# analog.net
KiCad netlist of a schematic drawn in Altium Designer
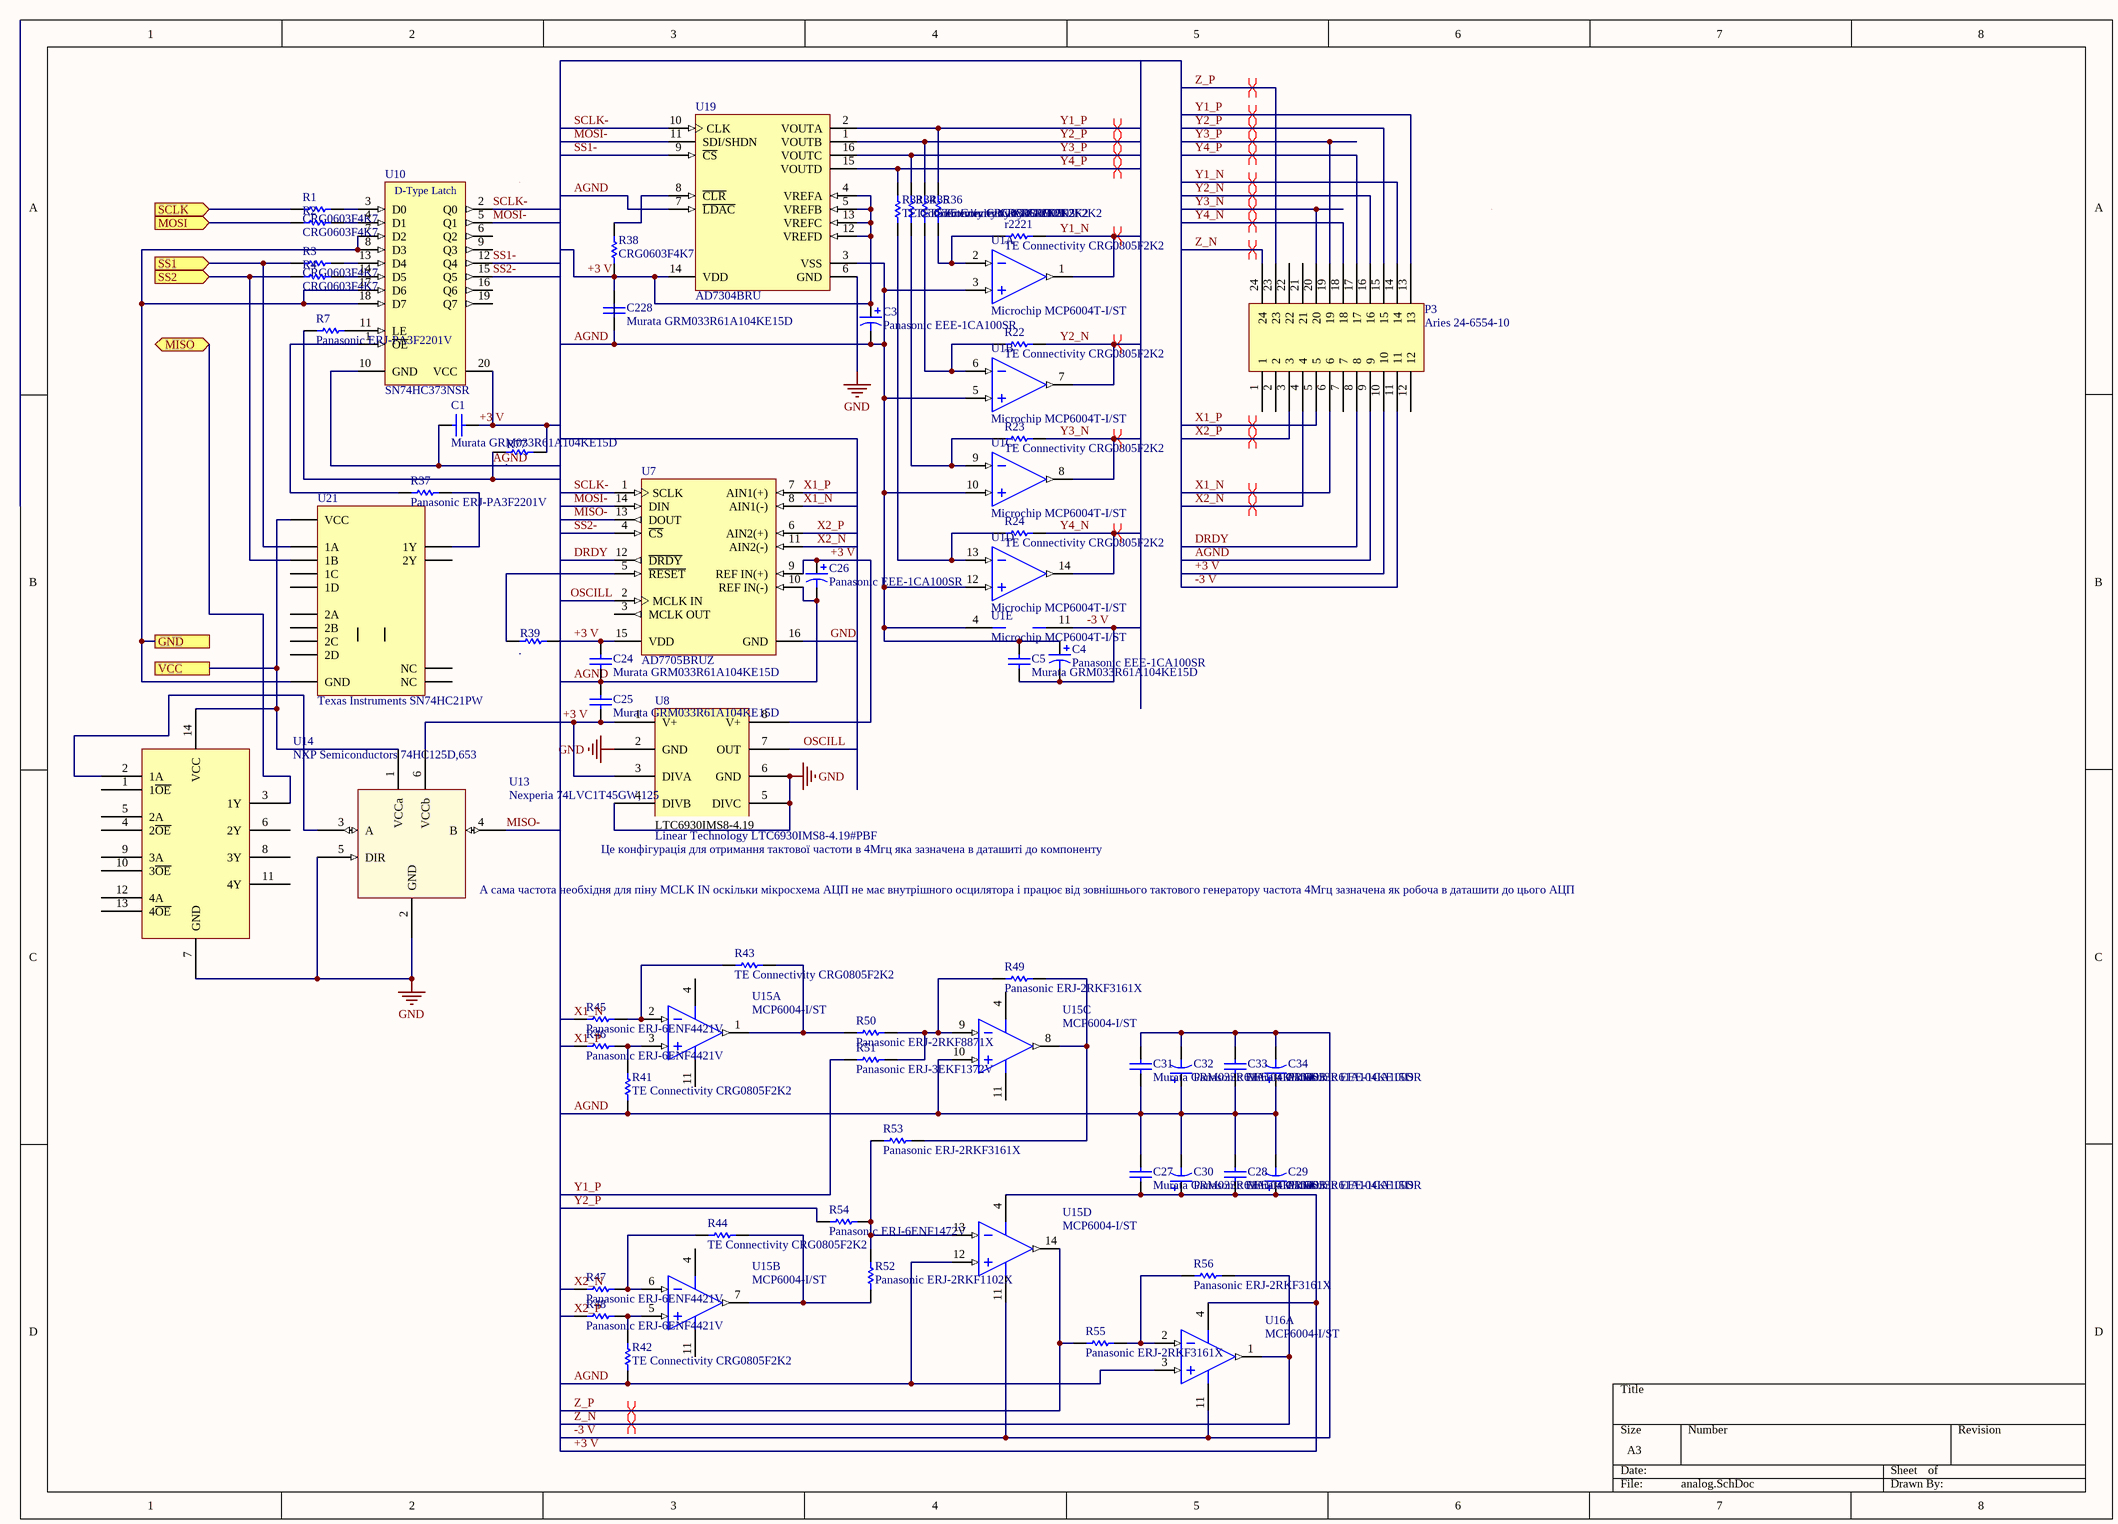
[diagram p0: analog.SchDoc]

(export (version "E")
  (design (tool "Eeschema 10.0.6"))
  (components
    (comp (ref "C1")
      (value "Murata GRM033R61A104KE15D")
      (footprint "201-cap")
      (description "Cap Ceramic 0.1uF 10V X5R 10% SMD 0201 85C Paper T/R")
      (fields (field (name "MANUFACTURER PART NUMBER") "GRM033R61A104KE15D"))
      (libsource (lib "My Personal Space") (part "GRM033R61A104KE15D"))
    )
    (comp (ref "C3")
      (value "Panasonic EEE-1CA100SR")
      (footprint "PCB-5c7lwdch6d5n3jfyiyq6-1")
      (description "Capacitor Alum Elec, 10uf, 16v, 20%, Scapacitor Alum Elec, 10uf, 16v, 20%, Smd, Full Reel")
      (libsource (lib "My Personal Space") (part "SYM-1d6cd72bfd77c2ab-3"))
    )
    (comp (ref "C4")
      (value "Panasonic EEE-1CA100SR")
      (footprint "PCB-5c7lwdch6d5n3jfyiyq6-1")
      (description "Capacitor Alum Elec, 10uf, 16v, 20%, Scapacitor Alum Elec, 10uf, 16v, 20%, Smd, Full Reel")
      (libsource (lib "My Personal Space") (part "SYM-1d6cd72bfd77c2ab-3"))
    )
    (comp (ref "C5")
      (value "Murata GRM033R61A104KE15D")
      (footprint "201-cap")
      (description "Cap Ceramic 0.1uF 10V X5R 10% SMD 0201 85C Paper T/R")
      (fields (field (name "MANUFACTURER PART NUMBER") "GRM033R61A104KE15D"))
      (libsource (lib "My Personal Space") (part "GRM033R61A104KE15D"))
    )
    (comp (ref "C24")
      (value "Murata GRM033R61A104KE15D")
      (footprint "201-cap")
      (description "Cap Ceramic 0.1uF 10V X5R 10% SMD 0201 85C Paper T/R")
      (fields (field (name "MANUFACTURER PART NUMBER") "GRM033R61A104KE15D"))
      (libsource (lib "My Personal Space") (part "GRM033R61A104KE15D"))
    )
    (comp (ref "C25")
      (value "Murata GRM033R61A104KE15D")
      (footprint "201-cap")
      (description "Cap Ceramic 0.1uF 10V X5R 10% SMD 0201 85C Paper T/R")
      (fields (field (name "MANUFACTURER PART NUMBER") "GRM033R61A104KE15D"))
      (libsource (lib "My Personal Space") (part "GRM033R61A104KE15D"))
    )
    (comp (ref "C26")
      (value "Panasonic EEE-1CA100SR")
      (footprint "PCB-5c7lwdch6d5n3jfyiyq6-1")
      (description "Capacitor Alum Elec, 10uf, 16v, 20%, Scapacitor Alum Elec, 10uf, 16v, 20%, Smd, Full Reel")
      (libsource (lib "My Personal Space") (part "SYM-1d6cd72bfd77c2ab-3"))
    )
    (comp (ref "C27")
      (value "Murata GRM033R61A104KE15D")
      (footprint "201-cap")
      (description "Cap Ceramic 0.1uF 10V X5R 10% SMD 0201 85C Paper T/R")
      (fields (field (name "MANUFACTURER PART NUMBER") "GRM033R61A104KE15D"))
      (libsource (lib "My Personal Space") (part "GRM033R61A104KE15D"))
    )
    (comp (ref "C28")
      (value "Murata GRM033R61A104KE15D")
      (footprint "201-cap")
      (description "Cap Ceramic 0.1uF 10V X5R 10% SMD 0201 85C Paper T/R")
      (fields (field (name "MANUFACTURER PART NUMBER") "GRM033R61A104KE15D"))
      (libsource (lib "My Personal Space") (part "GRM033R61A104KE15D"))
    )
    (comp (ref "C29")
      (value "Panasonic EEE-1CA100SR")
      (footprint "PCB-5c7lwdch6d5n3jfyiyq6-1")
      (description "Capacitor Alum Elec, 10uf, 16v, 20%, Scapacitor Alum Elec, 10uf, 16v, 20%, Smd, Full Reel")
      (libsource (lib "My Personal Space") (part "SYM-1d6cd72bfd77c2ab-3"))
    )
    (comp (ref "C30")
      (value "Panasonic EEE-1CA100SR")
      (footprint "PCB-5c7lwdch6d5n3jfyiyq6-1")
      (description "Capacitor Alum Elec, 10uf, 16v, 20%, Scapacitor Alum Elec, 10uf, 16v, 20%, Smd, Full Reel")
      (libsource (lib "My Personal Space") (part "SYM-1d6cd72bfd77c2ab-3"))
    )
    (comp (ref "C31")
      (value "Murata GRM033R61A104KE15D")
      (footprint "201-cap")
      (description "Cap Ceramic 0.1uF 10V X5R 10% SMD 0201 85C Paper T/R")
      (fields (field (name "MANUFACTURER PART NUMBER") "GRM033R61A104KE15D"))
      (libsource (lib "My Personal Space") (part "GRM033R61A104KE15D"))
    )
    (comp (ref "C32")
      (value "Panasonic EEE-1CA100SR")
      (footprint "PCB-5c7lwdch6d5n3jfyiyq6-1")
      (description "Capacitor Alum Elec, 10uf, 16v, 20%, Scapacitor Alum Elec, 10uf, 16v, 20%, Smd, Full Reel")
      (libsource (lib "My Personal Space") (part "SYM-1d6cd72bfd77c2ab-3"))
    )
    (comp (ref "C33")
      (value "Murata GRM033R61A104KE15D")
      (footprint "201-cap")
      (description "Cap Ceramic 0.1uF 10V X5R 10% SMD 0201 85C Paper T/R")
      (fields (field (name "MANUFACTURER PART NUMBER") "GRM033R61A104KE15D"))
      (libsource (lib "My Personal Space") (part "GRM033R61A104KE15D"))
    )
    (comp (ref "C34")
      (value "Panasonic EEE-1CA100SR")
      (footprint "PCB-5c7lwdch6d5n3jfyiyq6-1")
      (description "Capacitor Alum Elec, 10uf, 16v, 20%, Scapacitor Alum Elec, 10uf, 16v, 20%, Smd, Full Reel")
      (libsource (lib "My Personal Space") (part "SYM-1d6cd72bfd77c2ab-3"))
    )
    (comp (ref "C228")
      (value "Murata GRM033R61A104KE15D")
      (footprint "201-cap")
      (description "Cap Ceramic 0.1uF 10V X5R 10% SMD 0201 85C Paper T/R")
      (fields (field (name "MANUFACTURER PART NUMBER") "GRM033R61A104KE15D"))
      (libsource (lib "My Personal Space") (part "GRM033R61A104KE15D"))
    )
    (comp (ref "P3")
      (value "Aries 24-6554-10")
      (footprint "PCB-ekyruasckp3dwikngkzw-1")
      (description "Connector Test Socket Receptacle 24 Position 2.54mm Solder Straight Thru-Hole")
      (fields (field (name "MANUFACTURER PART NUMBER") "24-6554-10"))
      (libsource (lib "My Personal Space") (part "SYM-1a82d3838c70c545-1"))
    )
    (comp (ref "R1")
      (value "CRG0603F4K7")
      (footprint "RESC1609X50X30ML10T20")
      (description "Res Thick Film 0603 4.7K Ohm 1% 0.1W(1/10W) ±100ppm/C Pad SMD T/R")
      (libsource (lib "") (part "RES-2_1"))
    )
    (comp (ref "R2")
      (value "CRG0603F4K7")
      (footprint "RESC1609X50X30ML10T20")
      (description "Res Thick Film 0603 4.7K Ohm 1% 0.1W(1/10W) ±100ppm/C Pad SMD T/R")
      (libsource (lib "") (part "RES-2_1"))
    )
    (comp (ref "R3")
      (value "CRG0603F4K7")
      (footprint "RESC1609X50X30ML10T20")
      (description "Res Thick Film 0603 4.7K Ohm 1% 0.1W(1/10W) ±100ppm/C Pad SMD T/R")
      (libsource (lib "") (part "RES-2_1"))
    )
    (comp (ref "R4")
      (value "CRG0603F4K7")
      (footprint "RESC1609X50X30ML10T20")
      (description "Res Thick Film 0603 4.7K Ohm 1% 0.1W(1/10W) ±100ppm/C Pad SMD T/R")
      (libsource (lib "") (part "RES-2_1"))
    )
    (comp (ref "R7")
      (value "Panasonic ERJ-PA3F2201V")
      (footprint "RESC1608X55X30LL15T15")
      (description "Res Thick Film 0603 2.2K Ohm 1% 0.25W(1/4W) ±100ppm/C Pad SMD Automotive T/R")
      (fields (field (name "MANUFACTURER PART NUMBER") "ERJ-PA3F2201V"))
      (libsource (lib "My Personal Space") (part "RES-2"))
    )
    (comp (ref "R22")
      (value "TE Connectivity CRG0805F2K2")
      (footprint "RESC3216X70X50LL05T20")
      (description "Res Thick Film 0805 2.2K Ohm 1% 0.125W(1/8W) ±100ppm/C Pad SMD T/R")
      (fields (field (name "MANUFACTURER PART NUMBER") "CRG0805F2K2"))
      (libsource (lib "My Personal Space") (part "RES-2"))
    )
    (comp (ref "R23")
      (value "TE Connectivity CRG0805F2K2")
      (footprint "RESC3216X70X50LL05T20")
      (description "Res Thick Film 0805 2.2K Ohm 1% 0.125W(1/8W) ±100ppm/C Pad SMD T/R")
      (fields (field (name "MANUFACTURER PART NUMBER") "CRG0805F2K2"))
      (libsource (lib "My Personal Space") (part "RES-2"))
    )
    (comp (ref "R24")
      (value "TE Connectivity CRG0805F2K2")
      (footprint "RESC3216X70X50LL05T20")
      (description "Res Thick Film 0805 2.2K Ohm 1% 0.125W(1/8W) ±100ppm/C Pad SMD T/R")
      (fields (field (name "MANUFACTURER PART NUMBER") "CRG0805F2K2"))
      (libsource (lib "My Personal Space") (part "RES-2"))
    )
    (comp (ref "R33")
      (value "TE Connectivity CRG0805F2K2")
      (footprint "RESC3216X70X50LL05T20")
      (description "Res Thick Film 0805 2.2K Ohm 1% 0.125W(1/8W) ±100ppm/C Pad SMD T/R")
      (fields (field (name "MANUFACTURER PART NUMBER") "CRG0805F2K2"))
      (libsource (lib "My Personal Space") (part "RES-2"))
    )
    (comp (ref "R34")
      (value "TE Connectivity CRG0805F2K2")
      (footprint "RESC3216X70X50LL05T20")
      (description "Res Thick Film 0805 2.2K Ohm 1% 0.125W(1/8W) ±100ppm/C Pad SMD T/R")
      (fields (field (name "MANUFACTURER PART NUMBER") "CRG0805F2K2"))
      (libsource (lib "My Personal Space") (part "RES-2"))
    )
    (comp (ref "R35")
      (value "TE Connectivity CRG0805F2K2")
      (footprint "RESC3216X70X50LL05T20")
      (description "Res Thick Film 0805 2.2K Ohm 1% 0.125W(1/8W) ±100ppm/C Pad SMD T/R")
      (fields (field (name "MANUFACTURER PART NUMBER") "CRG0805F2K2"))
      (libsource (lib "My Personal Space") (part "RES-2"))
    )
    (comp (ref "R36")
      (value "TE Connectivity CRG0805F2K2")
      (footprint "RESC3216X70X50LL05T20")
      (description "Res Thick Film 0805 2.2K Ohm 1% 0.125W(1/8W) ±100ppm/C Pad SMD T/R")
      (fields (field (name "MANUFACTURER PART NUMBER") "CRG0805F2K2"))
      (libsource (lib "My Personal Space") (part "RES-2"))
    )
    (comp (ref "R37")
      (value "Panasonic ERJ-PA3F2201V")
      (footprint "RESC1608X55X30LL15T15")
      (description "Res Thick Film 0603 2.2K Ohm 1% 0.25W(1/4W) ±100ppm/C Pad SMD Automotive T/R")
      (fields (field (name "MANUFACTURER PART NUMBER") "ERJ-PA3F2201V"))
      (libsource (lib "My Personal Space") (part "RES-2"))
    )
    (comp (ref "R38")
      (value "CRG0603F4K7")
      (footprint "RESC1609X50X30ML10T20")
      (description "Res Thick Film 0603 4.7K Ohm 1% 0.1W(1/10W) ±100ppm/C Pad SMD T/R")
      (libsource (lib "") (part "RES-2_1"))
    )
    (comp (ref "R39")
      (value ".")
      (footprint "RESC1608X55X30LL15T15")
      (description "Res Thick Film 0603 2.2K Ohm 1% 0.25W(1/4W) ±100ppm/C Pad SMD Automotive T/R")
      (fields (field (name "MANUFACTURER PART NUMBER") "ERJ-PA3F2201V"))
      (libsource (lib "My Personal Space") (part "RES-2"))
    )
    (comp (ref "R41")
      (value "TE Connectivity CRG0805F2K2")
      (footprint "RESC3216X70X50LL05T20")
      (description "Res Thick Film 0805 2.2K Ohm 1% 0.125W(1/8W) ±100ppm/C Pad SMD T/R")
      (fields (field (name "MANUFACTURER PART NUMBER") "CRG0805F2K2"))
      (libsource (lib "My Personal Space") (part "RES-2"))
    )
    (comp (ref "R42")
      (value "TE Connectivity CRG0805F2K2")
      (footprint "RESC3216X70X50LL05T20")
      (description "Res Thick Film 0805 2.2K Ohm 1% 0.125W(1/8W) ±100ppm/C Pad SMD T/R")
      (fields (field (name "MANUFACTURER PART NUMBER") "CRG0805F2K2"))
      (libsource (lib "My Personal Space") (part "RES-2"))
    )
    (comp (ref "R43")
      (value "TE Connectivity CRG0805F2K2")
      (footprint "RESC3216X70X50LL05T20")
      (description "Res Thick Film 0805 2.2K Ohm 1% 0.125W(1/8W) ±100ppm/C Pad SMD T/R")
      (fields (field (name "MANUFACTURER PART NUMBER") "CRG0805F2K2"))
      (libsource (lib "My Personal Space") (part "RES-2"))
    )
    (comp (ref "R44")
      (value "TE Connectivity CRG0805F2K2")
      (footprint "RESC3216X70X50LL05T20")
      (description "Res Thick Film 0805 2.2K Ohm 1% 0.125W(1/8W) ±100ppm/C Pad SMD T/R")
      (fields (field (name "MANUFACTURER PART NUMBER") "CRG0805F2K2"))
      (libsource (lib "My Personal Space") (part "RES-2"))
    )
    (comp (ref "R45")
      (value "Panasonic ERJ-6ENF4421V")
      (footprint "RESC2013X70X40ML20T20")
      (description "RESISTOR, THICK FILM, 4.42KOHM, 125mW, ± 1%")
      (fields (field (name "MANUFACTURER PART NUMBER") "ERJ-6ENF4421V"))
      (libsource (lib "My Personal Space") (part "RES-2"))
    )
    (comp (ref "R46")
      (value "Panasonic ERJ-6ENF4421V")
      (footprint "RESC2013X70X40ML20T20")
      (description "RESISTOR, THICK FILM, 4.42KOHM, 125mW, ± 1%")
      (fields (field (name "MANUFACTURER PART NUMBER") "ERJ-6ENF4421V"))
      (libsource (lib "My Personal Space") (part "RES-2"))
    )
    (comp (ref "R47")
      (value "Panasonic ERJ-6ENF4421V")
      (footprint "RESC2013X70X40ML20T20")
      (description "RESISTOR, THICK FILM, 4.42KOHM, 125mW, ± 1%")
      (fields (field (name "MANUFACTURER PART NUMBER") "ERJ-6ENF4421V"))
      (libsource (lib "My Personal Space") (part "RES-2"))
    )
    (comp (ref "R48")
      (value "Panasonic ERJ-6ENF4421V")
      (footprint "RESC2013X70X40ML20T20")
      (description "RESISTOR, THICK FILM, 4.42KOHM, 125mW, ± 1%")
      (fields (field (name "MANUFACTURER PART NUMBER") "ERJ-6ENF4421V"))
      (libsource (lib "My Personal Space") (part "RES-2"))
    )
    (comp (ref "R49")
      (value "Panasonic ERJ-2RKF3161X")
      (footprint "RESC1005X40X25ML05T05")
      (description "Thick Film Resistors - SMD 0402 3.16Kohms 1% Tol")
      (fields (field (name "MANUFACTURER PART NUMBER") "ERJ-2RKF3161X"))
      (libsource (lib "My Personal Space") (part "RES-2"))
    )
    (comp (ref "R50")
      (value "Panasonic ERJ-2RKF8871X")
      (footprint "RESC1005X40X25ML05T05")
      (description "Thick Film Resistors - SMD 0402 8.87Kohms 1% Tol")
      (fields (field (name "MANUFACTURER PART NUMBER") "ERJ-2RKF8871X"))
      (libsource (lib "My Personal Space") (part "RES-2"))
    )
    (comp (ref "R51")
      (value "Panasonic ERJ-3EKF1372V")
      (footprint "RESC1608X55X30LL15T15")
      (description "Thick Film Resistors - SMD 0603 13.7Kohms 1% Tol")
      (fields (field (name "MANUFACTURER PART NUMBER") "ERJ-3EKF1372V"))
      (libsource (lib "My Personal Space") (part "RES-2"))
    )
    (comp (ref "R52")
      (value "Panasonic ERJ-2RKF1102X")
      (footprint "RESC1005X40X25ML05T05")
      (description "Res Thick Film 0402 11K Ohm 1% 1/10W ±100ppm/C Molded SMD Punched Carrier T/R")
      (fields (field (name "MANUFACTURER PART NUMBER") "ERJ-2RKF1102X"))
      (libsource (lib "My Personal Space") (part "RES-2"))
    )
    (comp (ref "R53")
      (value "Panasonic ERJ-2RKF3161X")
      (footprint "RESC1005X40X25ML05T05")
      (description "Thick Film Resistors - SMD 0402 3.16Kohms 1% Tol")
      (fields (field (name "MANUFACTURER PART NUMBER") "ERJ-2RKF3161X"))
      (libsource (lib "My Personal Space") (part "RES-2"))
    )
    (comp (ref "R54")
      (value "Panasonic ERJ-6ENF1472V")
      (footprint "RESC2013X70X40LL20T20")
      (description "Thick Film Resistors - SMD 0805 14.7Kohms 1% Tol")
      (fields (field (name "MANUFACTURER PART NUMBER") "ERJ-6ENF1472V"))
      (libsource (lib "My Personal Space") (part "RES-2"))
    )
    (comp (ref "R55")
      (value "Panasonic ERJ-2RKF3161X")
      (footprint "RESC1005X40X25ML05T05")
      (description "Thick Film Resistors - SMD 0402 3.16Kohms 1% Tol")
      (fields (field (name "MANUFACTURER PART NUMBER") "ERJ-2RKF3161X"))
      (libsource (lib "My Personal Space") (part "RES-2"))
    )
    (comp (ref "R56")
      (value "Panasonic ERJ-2RKF3161X")
      (footprint "RESC1005X40X25ML05T05")
      (description "Thick Film Resistors - SMD 0402 3.16Kohms 1% Tol")
      (fields (field (name "MANUFACTURER PART NUMBER") "ERJ-2RKF3161X"))
      (libsource (lib "My Personal Space") (part "RES-2"))
    )
    (comp (ref "R77")
      (value ".")
      (footprint "RESC1608X55X30LL15T15")
      (description "Res Thick Film 0603 2.2K Ohm 1% 0.25W(1/4W) ±100ppm/C Pad SMD Automotive T/R")
      (fields (field (name "MANUFACTURER PART NUMBER") "ERJ-PA3F2201V"))
      (libsource (lib "My Personal Space") (part "RES-2"))
    )
    (comp (ref "r2221")
      (value "TE Connectivity CRG0805F2K2")
      (footprint "RESC3216X70X50LL05T20")
      (description "Res Thick Film 0805 2.2K Ohm 1% 0.125W(1/8W) ±100ppm/C Pad SMD T/R")
      (fields (field (name "MANUFACTURER PART NUMBER") "CRG0805F2K2"))
      (libsource (lib "My Personal Space") (part "RES-2"))
    )
    (comp (ref "U1")
      (value "Microchip MCP6004T-I/ST")
      (footprint "PCB-qd5l9gv8ivpyuc7qt6ns-1")
      (description "MCP6004 Series 6 V 1 MHz SMT Low-Power Operational Amplifier - TSSOP-14")
      (libsource (lib "My Personal Space") (part "SYM-2145e8496108fe82-3"))
    )
    (comp (ref "U7")
      (value "AD7705BRUZ")
      (footprint "RU-16_N")
      (libsource (lib "My Personal Space") (part "ADI-AD7705-RU-16"))
    )
    (comp (ref "U8")
      (value "Linear Technology LTC6930IMS8-4.19#PBF")
      (footprint "PCB-f6jmd1xdx0tvjqeq7wyy-1")
      (fields (field (name "MANUFACTURER PART NUMBER") "LTC6930IMS8-5.00#PBF"))
      (libsource (lib "My Personal Space") (part "SYM-b5277c902da26ae0-1"))
    )
    (comp (ref "U10")
      (value "SN74HC373NSR")
      (footprint "PCB-mrivl7f71t22rnyfb9oh-1")
      (description "Octal Transparent D-Type Latches With 3-State Outputs 20-SO -40 to 85")
      (libsource (lib "My Personal Space") (part "SYM-209beb569da8ff5c-1"))
    )
    (comp (ref "U13")
      (value "Nexperia 74LVC1T45GW,125")
      (footprint "PCB-2kx227qvn7pif93bx96a-1")
      (description "74LVC1T45; 74LVCH1T45 - Dual supply translating transceiver; 3-state")
      (fields (field (name "MANUFACTURER PART NUMBER") "74LVC1T45GW,125"))
      (libsource (lib "My Personal Space") (part "SYM-9dea5051caa8422d-1"))
    )
    (comp (ref "U14")
      (value "NXP Semiconductors 74HC125D,653")
      (footprint "SO14")
      (description "74HC Series 6 V Surface Mount 3-State Quad Buffer/Line Driver - SOIC-14")
      (fields (field (name "MANUFACTURER PART NUMBER") "74HC125D,653"))
      (libsource (lib "My Personal Space") (part "SYM-e63b2fae16a839fc-1"))
    )
    (comp (ref "U15")
      (value "MCP6004-I/ST")
      (footprint "TSSOP-ST14_L")
      (description "1 MHz, Low-Power Operational Amplifier, 14-Pin TSSOP, Industrial Temperature")
      (libsource (lib "My Personal Space") (part "AMP-OPA-MCP6004-IL14"))
    )
    (comp (ref "U16")
      (value "MCP6004-I/ST")
      (footprint "TSSOP-ST14_L")
      (description "1 MHz, Low-Power Operational Amplifier, 14-Pin TSSOP, Industrial Temperature")
      (libsource (lib "My Personal Space") (part "AMP-OPA-MCP6004-IL14"))
    )
    (comp (ref "U19")
      (value "AD7304BRU")
      (footprint "RU-16_M")
      (libsource (lib "My Personal Space") (part "ADI-AD7304-RU-16"))
    )
    (comp (ref "U21")
      (value "Texas Instruments SN74HC21PW")
      (footprint "PCB-zlibg0os7u66y1b7c6dv-1")
      (description "AND Gate 2-Element 4-IN CMOS 14-Pin TSSOP Tube")
      (fields (field (name "MANUFACTURER PART NUMBER") "SN74HC21PW"))
      (libsource (lib "My Personal Space") (part "SYM-6615af12324ab9d2-2"))
    )
  )
  (nets
    (net (code "1") (name "/+3 V") (class "Default")
      (node (ref "C1") (pin "2") (pinfunction "2_2") (pintype "passive"))
      (node (ref "C228") (pin "1") (pinfunction "1_1") (pintype "passive"))
      (node (ref "C24") (pin "1") (pinfunction "1_1") (pintype "passive"))
      (node (ref "C25") (pin "2") (pinfunction "2_2") (pintype "passive"))
      (node (ref "C26") (pin "1") (pinfunction "1_1") (pintype "passive"))
      (node (ref "C27") (pin "2") (pinfunction "2_2") (pintype "passive"))
      (node (ref "C28") (pin "2") (pinfunction "2_2") (pintype "passive"))
      (node (ref "C29") (pin "1") (pinfunction "1_1") (pintype "passive"))
      (node (ref "C3") (pin "1") (pinfunction "1_1") (pintype "passive"))
      (node (ref "C30") (pin "1") (pinfunction "1_1") (pintype "passive"))
      (node (ref "P3") (pin "10") (pinfunction "10_10") (pintype "passive"))
      (node (ref "R38") (pin "1") (pinfunction "1_1") (pintype "passive"))
      (node (ref "R39") (pin "2") (pinfunction "2_2") (pintype "passive"))
      (node (ref "R77") (pin "2") (pinfunction "2_2") (pintype "passive"))
      (node (ref "U10") (pin "20") (pinfunction "VCC_20") (pintype "power_in"))
      (node (ref "U13") (pin "6") (pinfunction "VCCb_6") (pintype "power_in"))
      (node (ref "U15") (pin "4") (pinfunction "VDD_4") (pintype "power_in"))
      (node (ref "U16") (pin "4") (pinfunction "VDD_4") (pintype "power_in"))
      (node (ref "U19") (pin "12") (pinfunction "VREFD_12") (pintype "input"))
      (node (ref "U19") (pin "13") (pinfunction "VREFC_13") (pintype "input"))
      (node (ref "U19") (pin "14") (pinfunction "VDD_14") (pintype "power_in"))
      (node (ref "U19") (pin "4") (pinfunction "VREFA_4") (pintype "input"))
      (node (ref "U19") (pin "5") (pinfunction "VREFB_5") (pintype "input"))
      (node (ref "U7") (pin "15") (pinfunction "VDD_15") (pintype "power_in"))
      (node (ref "U7") (pin "9") (pinfunction "REF_IN(+)_9") (pintype "input"))
      (node (ref "U8") (pin "1") (pinfunction "V+_1") (pintype "passive"))
      (node (ref "U8") (pin "3") (pinfunction "DIVA_3") (pintype "passive"))
      (node (ref "U8") (pin "8") (pinfunction "V+_8") (pintype "passive"))
    )
    (net (code "2") (name "/-3 V") (class "Default")
      (node (ref "C31") (pin "1") (pinfunction "1_1") (pintype "passive"))
      (node (ref "C32") (pin "2") (pinfunction "2_2") (pintype "passive"))
      (node (ref "C33") (pin "1") (pinfunction "1_1") (pintype "passive"))
      (node (ref "C34") (pin "2") (pinfunction "2_2") (pintype "passive"))
      (node (ref "C4") (pin "2") (pinfunction "2_2") (pintype "passive"))
      (node (ref "C5") (pin "2") (pinfunction "2_2") (pintype "passive"))
      (node (ref "P3") (pin "11") (pinfunction "11_11") (pintype "passive"))
      (node (ref "U1") (pin "11") (pinfunction "VSS_11") (pintype "power_in"))
      (node (ref "U15") (pin "11") (pinfunction "VSS_11") (pintype "power_in"))
      (node (ref "U16") (pin "11") (pinfunction "VSS_11") (pintype "power_in"))
    )
    (net (code "3") (name "/AGND") (class "Default")
      (node (ref "C1") (pin "1") (pinfunction "1_1") (pintype "passive"))
      (node (ref "C228") (pin "2") (pinfunction "2_2") (pintype "passive"))
      (node (ref "C24") (pin "2") (pinfunction "2_2") (pintype "passive"))
      (node (ref "C25") (pin "1") (pinfunction "1_1") (pintype "passive"))
      (node (ref "C26") (pin "2") (pinfunction "2_2") (pintype "passive"))
      (node (ref "C27") (pin "1") (pinfunction "1_1") (pintype "passive"))
      (node (ref "C28") (pin "1") (pinfunction "1_1") (pintype "passive"))
      (node (ref "C29") (pin "2") (pinfunction "2_2") (pintype "passive"))
      (node (ref "C3") (pin "2") (pinfunction "2_2") (pintype "passive"))
      (node (ref "C30") (pin "2") (pinfunction "2_2") (pintype "passive"))
      (node (ref "C31") (pin "2") (pinfunction "2_2") (pintype "passive"))
      (node (ref "C32") (pin "1") (pinfunction "1_1") (pintype "passive"))
      (node (ref "C33") (pin "2") (pinfunction "2_2") (pintype "passive"))
      (node (ref "C34") (pin "1") (pinfunction "1_1") (pintype "passive"))
      (node (ref "C4") (pin "1") (pinfunction "1_1") (pintype "passive"))
      (node (ref "C5") (pin "1") (pinfunction "1_1") (pintype "passive"))
      (node (ref "P3") (pin "9") (pinfunction "9_9") (pintype "passive"))
      (node (ref "R41") (pin "1") (pinfunction "1_1") (pintype "passive"))
      (node (ref "R42") (pin "1") (pinfunction "1_1") (pintype "passive"))
      (node (ref "R7") (pin "1") (pinfunction "1_1") (pintype "passive"))
      (node (ref "R77") (pin "1") (pinfunction "1_1") (pintype "passive"))
      (node (ref "U1") (pin "10") (pinfunction "INC+_10") (pintype "input"))
      (node (ref "U1") (pin "12") (pinfunction "IND+_12") (pintype "input"))
      (node (ref "U1") (pin "3") (pinfunction "INA+_3") (pintype "input"))
      (node (ref "U1") (pin "4") (pinfunction "VDD_4") (pintype "power_in"))
      (node (ref "U1") (pin "5") (pinfunction "INB+_5") (pintype "input"))
      (node (ref "U10") (pin "10") (pinfunction "GND_10") (pintype "power_in"))
      (node (ref "U15") (pin "10") (pinfunction "VINC+_10") (pintype "input"))
      (node (ref "U15") (pin "12") (pinfunction "VIND+_12") (pintype "input"))
      (node (ref "U16") (pin "3") (pinfunction "VINA+_3") (pintype "input"))
      (node (ref "U19") (pin "3") (pinfunction "VSS_3") (pintype "power_in"))
      (node (ref "U19") (pin "7") (pinfunction "~{LDAC}_7") (pintype "input"))
      (node (ref "U7") (pin "10") (pinfunction "REF_IN(-)_10") (pintype "input"))
    )
    (net (code "4") (name "/DRDY") (class "Default")
      (node (ref "P3") (pin "8") (pinfunction "8_8") (pintype "passive"))
      (node (ref "U7") (pin "12") (pinfunction "~{DRDY}_12") (pintype "output"))
    )
    (net (code "5") (name "/MISO") (class "Default")
      (node (ref "U14") (pin "3") (pinfunction "1Y_3") (pintype "passive"))
    )
    (net (code "6") (name "/MISO-") (class "Default")
      (node (ref "U13") (pin "4") (pinfunction "B_4") (pintype "bidirectional"))
      (node (ref "U7") (pin "13") (pinfunction "DOUT_13") (pintype "output"))
    )
    (net (code "7") (name "/MOSI") (class "Default")
      (node (ref "R2") (pin "1") (pinfunction "1_1") (pintype "passive"))
    )
    (net (code "8") (name "/MOSI-") (class "Default")
      (node (ref "U10") (pin "5") (pinfunction "Q1_5") (pintype "output"))
      (node (ref "U19") (pin "11") (pinfunction "SDI/SHDN_11") (pintype "passive"))
      (node (ref "U7") (pin "14") (pinfunction "DIN_14") (pintype "input"))
    )
    (net (code "9") (name "/OSCILL") (class "Default")
      (node (ref "U7") (pin "2") (pinfunction "MCLK_IN_2") (pintype "input"))
      (node (ref "U8") (pin "7") (pinfunction "OUT_7") (pintype "passive"))
    )
    (net (code "10") (name "/SCLK") (class "Default")
      (node (ref "R1") (pin "1") (pinfunction "1_1") (pintype "passive"))
    )
    (net (code "11") (name "/SCLK-") (class "Default")
      (node (ref "U10") (pin "2") (pinfunction "Q0_2") (pintype "output"))
      (node (ref "U19") (pin "10") (pinfunction "CLK_10") (pintype "input"))
      (node (ref "U7") (pin "1") (pinfunction "SCLK_1") (pintype "input"))
    )
    (net (code "12") (name "/SS1") (class "Default")
      (node (ref "R3") (pin "1") (pinfunction "1_1") (pintype "passive"))
      (node (ref "U21") (pin "1") (pinfunction "1A_1") (pintype "passive"))
    )
    (net (code "13") (name "/SS1-") (class "Default")
      (node (ref "U10") (pin "12") (pinfunction "Q4_12") (pintype "output"))
      (node (ref "U19") (pin "9") (pinfunction "~{CS}_9") (pintype "input"))
    )
    (net (code "14") (name "/SS2") (class "Default")
      (node (ref "R4") (pin "1") (pinfunction "1_1") (pintype "passive"))
      (node (ref "U21") (pin "2") (pinfunction "1B_2") (pintype "passive"))
    )
    (net (code "15") (name "/SS2-") (class "Default")
      (node (ref "U10") (pin "15") (pinfunction "Q5_15") (pintype "output"))
      (node (ref "U7") (pin "4") (pinfunction "~{CS}_4") (pintype "input"))
    )
    (net (code "16") (name "/VCC") (class "Default")
      (node (ref "U13") (pin "1") (pinfunction "VCCa_1") (pintype "power_in"))
      (node (ref "U14") (pin "14") (pinfunction "VCC_14") (pintype "passive"))
      (node (ref "U21") (pin "14") (pinfunction "VCC_14") (pintype "passive"))
    )
    (net (code "17") (name "/X1_N") (class "Default")
      (node (ref "P3") (pin "6") (pinfunction "6_6") (pintype "passive"))
      (node (ref "R45") (pin "1") (pinfunction "1_1") (pintype "passive"))
      (node (ref "U7") (pin "8") (pinfunction "AIN1(-)_8") (pintype "input"))
    )
    (net (code "18") (name "/X1_P") (class "Default")
      (node (ref "P3") (pin "5") (pinfunction "5_5") (pintype "passive"))
      (node (ref "R46") (pin "1") (pinfunction "1_1") (pintype "passive"))
      (node (ref "U7") (pin "7") (pinfunction "AIN1(+)_7") (pintype "input"))
    )
    (net (code "19") (name "/X2_N") (class "Default")
      (node (ref "P3") (pin "4") (pinfunction "4_4") (pintype "passive"))
      (node (ref "R47") (pin "1") (pinfunction "1_1") (pintype "passive"))
      (node (ref "U7") (pin "11") (pinfunction "AIN2(-)_11") (pintype "input"))
    )
    (net (code "20") (name "/X2_P") (class "Default")
      (node (ref "P3") (pin "3") (pinfunction "3_3") (pintype "passive"))
      (node (ref "R48") (pin "1") (pinfunction "1_1") (pintype "passive"))
      (node (ref "U7") (pin "6") (pinfunction "AIN2(+)_6") (pintype "input"))
    )
    (net (code "21") (name "/Y1_N") (class "Default")
      (node (ref "P3") (pin "14") (pinfunction "14_14") (pintype "passive"))
      (node (ref "U1") (pin "1") (pinfunction "OUTA_1") (pintype "output"))
      (node (ref "r2221") (pin "2") (pinfunction "2_2") (pintype "passive"))
    )
    (net (code "22") (name "/Y1_P") (class "Default")
      (node (ref "P3") (pin "13") (pinfunction "13_13") (pintype "passive"))
      (node (ref "R36") (pin "2") (pinfunction "2_2") (pintype "passive"))
      (node (ref "R51") (pin "1") (pinfunction "1_1") (pintype "passive"))
      (node (ref "U19") (pin "2") (pinfunction "VOUTA_2") (pintype "tri_state"))
    )
    (net (code "23") (name "/Y2_N") (class "Default")
      (node (ref "P3") (pin "16") (pinfunction "16_16") (pintype "passive"))
      (node (ref "R22") (pin "2") (pinfunction "2_2") (pintype "passive"))
      (node (ref "U1") (pin "7") (pinfunction "OUTB_7") (pintype "output"))
    )
    (net (code "24") (name "/Y2_P") (class "Default")
      (node (ref "P3") (pin "15") (pinfunction "15_15") (pintype "passive"))
      (node (ref "R35") (pin "2") (pinfunction "2_2") (pintype "passive"))
      (node (ref "R54") (pin "1") (pinfunction "1_1") (pintype "passive"))
      (node (ref "U19") (pin "1") (pinfunction "VOUTB_1") (pintype "tri_state"))
    )
    (net (code "25") (name "/Y3_N") (class "Default")
      (node (ref "P3") (pin "20") (pinfunction "20_20") (pintype "passive"))
      (node (ref "R23") (pin "2") (pinfunction "2_2") (pintype "passive"))
      (node (ref "U1") (pin "8") (pinfunction "OUTC_8") (pintype "output"))
    )
    (net (code "26") (name "/Y3_P") (class "Default")
      (node (ref "P3") (pin "19") (pinfunction "19_19") (pintype "passive"))
      (node (ref "R34") (pin "2") (pinfunction "2_2") (pintype "passive"))
      (node (ref "U19") (pin "16") (pinfunction "VOUTC_16") (pintype "tri_state"))
    )
    (net (code "27") (name "/Y4_N") (class "Default")
      (node (ref "P3") (pin "18") (pinfunction "18_18") (pintype "passive"))
      (node (ref "R24") (pin "2") (pinfunction "2_2") (pintype "passive"))
      (node (ref "U1") (pin "14") (pinfunction "OUTD_14") (pintype "output"))
    )
    (net (code "28") (name "/Y4_P") (class "Default")
      (node (ref "P3") (pin "17") (pinfunction "17_17") (pintype "passive"))
      (node (ref "R33") (pin "2") (pinfunction "2_2") (pintype "passive"))
      (node (ref "U19") (pin "15") (pinfunction "VOUTD_15") (pintype "tri_state"))
    )
    (net (code "29") (name "/Z_N") (class "Default")
      (node (ref "P3") (pin "24") (pinfunction "24_24") (pintype "passive"))
      (node (ref "R56") (pin "2") (pinfunction "2_2") (pintype "passive"))
      (node (ref "U16") (pin "1") (pinfunction "VOUTA_1") (pintype "output"))
    )
    (net (code "30") (name "/Z_P") (class "Default")
      (node (ref "P3") (pin "23") (pinfunction "23_23") (pintype "passive"))
      (node (ref "R55") (pin "1") (pinfunction "1_1") (pintype "passive"))
      (node (ref "U15") (pin "14") (pinfunction "VOUTD_14") (pintype "output"))
    )
    (net (code "31") (name "GND") (class "Default")
      (node (ref "U10") (pin "17") (pinfunction "D6_17") (pintype "input"))
      (node (ref "U10") (pin "18") (pinfunction "D7_18") (pintype "input"))
      (node (ref "U10") (pin "7") (pinfunction "D2_7") (pintype "input"))
      (node (ref "U10") (pin "8") (pinfunction "D3_8") (pintype "input"))
      (node (ref "U13") (pin "2") (pinfunction "GND_2") (pintype "power_in"))
      (node (ref "U13") (pin "5") (pinfunction "DIR_5") (pintype "input"))
      (node (ref "U14") (pin "7") (pinfunction "GND_7") (pintype "passive"))
      (node (ref "U19") (pin "6") (pinfunction "GND_6") (pintype "power_in"))
      (node (ref "U21") (pin "7") (pinfunction "GND_7") (pintype "passive"))
      (node (ref "U7") (pin "16") (pinfunction "GND_16") (pintype "power_in"))
      (node (ref "U8") (pin "2") (pinfunction "GND_2") (pintype "passive"))
      (node (ref "U8") (pin "4") (pinfunction "DIVB_4") (pintype "passive"))
      (node (ref "U8") (pin "5") (pinfunction "DIVC_5") (pintype "passive"))
      (node (ref "U8") (pin "6") (pinfunction "GND_6") (pintype "passive"))
    )
    (net (code "32") (name "Net-(U1A-INA-)") (class "Default")
      (node (ref "R36") (pin "1") (pinfunction "1_1") (pintype "passive"))
      (node (ref "U1") (pin "2") (pinfunction "INA-_2") (pintype "input"))
      (node (ref "r2221") (pin "1") (pinfunction "1_1") (pintype "passive"))
    )
    (net (code "33") (name "Net-(U1B-INB-)") (class "Default")
      (node (ref "R22") (pin "1") (pinfunction "1_1") (pintype "passive"))
      (node (ref "R35") (pin "1") (pinfunction "1_1") (pintype "passive"))
      (node (ref "U1") (pin "6") (pinfunction "INB-_6") (pintype "input"))
    )
    (net (code "34") (name "Net-(U1C-INC-)") (class "Default")
      (node (ref "R23") (pin "1") (pinfunction "1_1") (pintype "passive"))
      (node (ref "R34") (pin "1") (pinfunction "1_1") (pintype "passive"))
      (node (ref "U1") (pin "9") (pinfunction "INC-_9") (pintype "input"))
    )
    (net (code "35") (name "Net-(U1D-IND-)") (class "Default")
      (node (ref "R24") (pin "1") (pinfunction "1_1") (pintype "passive"))
      (node (ref "R33") (pin "1") (pinfunction "1_1") (pintype "passive"))
      (node (ref "U1") (pin "13") (pinfunction "IND-_13") (pintype "input"))
    )
    (net (code "36") (name "Net-(U7-~{RESET})") (class "Default")
      (node (ref "R39") (pin "1") (pinfunction "1_1") (pintype "passive"))
      (node (ref "U7") (pin "5") (pinfunction "~{RESET}_5") (pintype "input"))
    )
    (net (code "37") (name "Net-(U10-D0)") (class "Default")
      (node (ref "R1") (pin "2") (pinfunction "2_2") (pintype "passive"))
      (node (ref "U10") (pin "3") (pinfunction "D0_3") (pintype "input"))
    )
    (net (code "38") (name "Net-(U10-D1)") (class "Default")
      (node (ref "R2") (pin "2") (pinfunction "2_2") (pintype "passive"))
      (node (ref "U10") (pin "4") (pinfunction "D1_4") (pintype "input"))
    )
    (net (code "39") (name "Net-(U10-D4)") (class "Default")
      (node (ref "R3") (pin "2") (pinfunction "2_2") (pintype "passive"))
      (node (ref "U10") (pin "13") (pinfunction "D4_13") (pintype "input"))
    )
    (net (code "40") (name "Net-(U10-D5)") (class "Default")
      (node (ref "R4") (pin "2") (pinfunction "2_2") (pintype "passive"))
      (node (ref "U10") (pin "14") (pinfunction "D5_14") (pintype "input"))
    )
    (net (code "41") (name "Net-(U10-LE)") (class "Default")
      (node (ref "R7") (pin "2") (pinfunction "2_2") (pintype "passive"))
      (node (ref "U10") (pin "11") (pinfunction "LE_11") (pintype "input"))
    )
    (net (code "42") (name "Net-(U10-~{OE})") (class "Default")
      (node (ref "R37") (pin "1") (pinfunction "1_1") (pintype "passive"))
      (node (ref "U10") (pin "1") (pinfunction "~{OE}_1") (pintype "input"))
    )
    (net (code "43") (name "Net-(U13-A)") (class "Default")
      (node (ref "U13") (pin "3") (pinfunction "A_3") (pintype "bidirectional"))
      (node (ref "U14") (pin "2") (pinfunction "1A_2") (pintype "passive"))
    )
    (net (code "44") (name "Net-(U15A-VINA+)") (class "Default")
      (node (ref "R41") (pin "2") (pinfunction "2_2") (pintype "passive"))
      (node (ref "R46") (pin "2") (pinfunction "2_2") (pintype "passive"))
      (node (ref "U15") (pin "3") (pinfunction "VINA+_3") (pintype "input"))
    )
    (net (code "45") (name "Net-(U15A-VINA-)") (class "Default")
      (node (ref "R43") (pin "2") (pinfunction "2_2") (pintype "passive"))
      (node (ref "R45") (pin "2") (pinfunction "2_2") (pintype "passive"))
      (node (ref "U15") (pin "2") (pinfunction "VINA-_2") (pintype "input"))
    )
    (net (code "46") (name "Net-(U15A-VOUTA)") (class "Default")
      (node (ref "R43") (pin "1") (pinfunction "1_1") (pintype "passive"))
      (node (ref "R50") (pin "1") (pinfunction "1_1") (pintype "passive"))
      (node (ref "U15") (pin "1") (pinfunction "VOUTA_1") (pintype "output"))
    )
    (net (code "47") (name "Net-(U15B-VINB+)") (class "Default")
      (node (ref "R42") (pin "2") (pinfunction "2_2") (pintype "passive"))
      (node (ref "R48") (pin "2") (pinfunction "2_2") (pintype "passive"))
      (node (ref "U15") (pin "5") (pinfunction "VINB+_5") (pintype "input"))
    )
    (net (code "48") (name "Net-(U15B-VINB-)") (class "Default")
      (node (ref "R44") (pin "2") (pinfunction "2_2") (pintype "passive"))
      (node (ref "R47") (pin "2") (pinfunction "2_2") (pintype "passive"))
      (node (ref "U15") (pin "6") (pinfunction "VINB-_6") (pintype "input"))
    )
    (net (code "49") (name "Net-(U15B-VOUTB)") (class "Default")
      (node (ref "R44") (pin "1") (pinfunction "1_1") (pintype "passive"))
      (node (ref "R52") (pin "1") (pinfunction "1_1") (pintype "passive"))
      (node (ref "U15") (pin "7") (pinfunction "VOUTB_7") (pintype "output"))
    )
    (net (code "50") (name "Net-(U15C-VINC-)") (class "Default")
      (node (ref "R49") (pin "1") (pinfunction "1_1") (pintype "passive"))
      (node (ref "R50") (pin "2") (pinfunction "2_2") (pintype "passive"))
      (node (ref "R51") (pin "2") (pinfunction "2_2") (pintype "passive"))
      (node (ref "U15") (pin "9") (pinfunction "VINC-_9") (pintype "input"))
    )
    (net (code "51") (name "Net-(U15C-VOUTC)") (class "Default")
      (node (ref "R49") (pin "2") (pinfunction "2_2") (pintype "passive"))
      (node (ref "R53") (pin "2") (pinfunction "2_2") (pintype "passive"))
      (node (ref "U15") (pin "8") (pinfunction "VOUTC_8") (pintype "output"))
    )
    (net (code "52") (name "Net-(U15D-VIND-)") (class "Default")
      (node (ref "R52") (pin "2") (pinfunction "2_2") (pintype "passive"))
      (node (ref "R53") (pin "1") (pinfunction "1_1") (pintype "passive"))
      (node (ref "R54") (pin "2") (pinfunction "2_2") (pintype "passive"))
      (node (ref "U15") (pin "13") (pinfunction "VIND-_13") (pintype "input"))
    )
    (net (code "53") (name "Net-(U16A-VINA-)") (class "Default")
      (node (ref "R55") (pin "2") (pinfunction "2_2") (pintype "passive"))
      (node (ref "R56") (pin "1") (pinfunction "1_1") (pintype "passive"))
      (node (ref "U16") (pin "2") (pinfunction "VINA-_2") (pintype "input"))
    )
    (net (code "54") (name "Net-(U19-~{CLR})") (class "Default")
      (node (ref "R38") (pin "2") (pinfunction "2_2") (pintype "passive"))
      (node (ref "U19") (pin "8") (pinfunction "~{CLR}_8") (pintype "input"))
    )
    (net (code "55") (name "Net-(U21-1Y)") (class "Default")
      (node (ref "R37") (pin "2") (pinfunction "2_2") (pintype "passive"))
      (node (ref "U21") (pin "6") (pinfunction "1Y_6") (pintype "passive"))
    )
    (net (code "56") (name "unconnected-(P3-Pad1)") (class "Default")
      (node (ref "P3") (pin "1") (pinfunction "1_1") (pintype "passive"))
    )
    (net (code "57") (name "unconnected-(P3-Pad2)") (class "Default")
      (node (ref "P3") (pin "2") (pinfunction "2_2") (pintype "passive"))
    )
    (net (code "58") (name "unconnected-(P3-Pad7)") (class "Default")
      (node (ref "P3") (pin "7") (pinfunction "7_7") (pintype "passive"))
    )
    (net (code "59") (name "unconnected-(P3-Pad12)") (class "Default")
      (node (ref "P3") (pin "12") (pinfunction "12_12") (pintype "passive"))
    )
    (net (code "60") (name "unconnected-(P3-Pad21)") (class "Default")
      (node (ref "P3") (pin "21") (pinfunction "21_21") (pintype "passive"))
    )
    (net (code "61") (name "unconnected-(P3-Pad22)") (class "Default")
      (node (ref "P3") (pin "22") (pinfunction "22_22") (pintype "passive"))
    )
    (net (code "62") (name "unconnected-(U7-MCLK_OUT-Pad3)") (class "Default")
      (node (ref "U7") (pin "3") (pinfunction "MCLK_OUT_3") (pintype "output"))
    )
    (net (code "63") (name "unconnected-(U10-Q2-Pad6)") (class "Default")
      (node (ref "U10") (pin "6") (pinfunction "Q2_6") (pintype "output"))
    )
    (net (code "64") (name "unconnected-(U10-Q3-Pad9)") (class "Default")
      (node (ref "U10") (pin "9") (pinfunction "Q3_9") (pintype "output"))
    )
    (net (code "65") (name "unconnected-(U10-Q6-Pad16)") (class "Default")
      (node (ref "U10") (pin "16") (pinfunction "Q6_16") (pintype "output"))
    )
    (net (code "66") (name "unconnected-(U10-Q7-Pad19)") (class "Default")
      (node (ref "U10") (pin "19") (pinfunction "Q7_19") (pintype "output"))
    )
    (net (code "67") (name "unconnected-(U14-1~{OE}-Pad1)") (class "Default")
      (node (ref "U14") (pin "1") (pinfunction "1~{OE}_1") (pintype "passive"))
    )
    (net (code "68") (name "unconnected-(U14-2A-Pad5)") (class "Default")
      (node (ref "U14") (pin "5") (pinfunction "2A_5") (pintype "passive"))
    )
    (net (code "69") (name "unconnected-(U14-2Y-Pad6)") (class "Default")
      (node (ref "U14") (pin "6") (pinfunction "2Y_6") (pintype "passive"))
    )
    (net (code "70") (name "unconnected-(U14-2~{OE}-Pad4)") (class "Default")
      (node (ref "U14") (pin "4") (pinfunction "2~{OE}_4") (pintype "passive"))
    )
    (net (code "71") (name "unconnected-(U14-3A-Pad9)") (class "Default")
      (node (ref "U14") (pin "9") (pinfunction "3A_9") (pintype "passive"))
    )
    (net (code "72") (name "unconnected-(U14-3Y-Pad8)") (class "Default")
      (node (ref "U14") (pin "8") (pinfunction "3Y_8") (pintype "passive"))
    )
    (net (code "73") (name "unconnected-(U14-3~{OE}-Pad10)") (class "Default")
      (node (ref "U14") (pin "10") (pinfunction "3~{OE}_10") (pintype "passive"))
    )
    (net (code "74") (name "unconnected-(U14-4A-Pad12)") (class "Default")
      (node (ref "U14") (pin "12") (pinfunction "4A_12") (pintype "passive"))
    )
    (net (code "75") (name "unconnected-(U14-4Y-Pad11)") (class "Default")
      (node (ref "U14") (pin "11") (pinfunction "4Y_11") (pintype "passive"))
    )
    (net (code "76") (name "unconnected-(U14-4~{OE}-Pad13)") (class "Default")
      (node (ref "U14") (pin "13") (pinfunction "4~{OE}_13") (pintype "passive"))
    )
    (net (code "77") (name "unconnected-(U15A-VDD-Pad4)") (class "Default")
      (node (ref "U15") (pin "4") (pinfunction "VDD_4") (pintype "power_in"))
    )
    (net (code "78") (name "unconnected-(U15A-VSS-Pad11)") (class "Default")
      (node (ref "U15") (pin "11") (pinfunction "VSS_11") (pintype "power_in"))
    )
    (net (code "79") (name "unconnected-(U15B-VDD-Pad4)") (class "Default")
      (node (ref "U15") (pin "4") (pinfunction "VDD_4") (pintype "power_in"))
    )
    (net (code "80") (name "unconnected-(U15B-VSS-Pad11)") (class "Default")
      (node (ref "U15") (pin "11") (pinfunction "VSS_11") (pintype "power_in"))
    )
    (net (code "81") (name "unconnected-(U15C-VDD-Pad4)") (class "Default")
      (node (ref "U15") (pin "4") (pinfunction "VDD_4") (pintype "power_in"))
    )
    (net (code "82") (name "unconnected-(U15C-VSS-Pad11)") (class "Default")
      (node (ref "U15") (pin "11") (pinfunction "VSS_11") (pintype "power_in"))
    )
    (net (code "83") (name "unconnected-(U21-1C-Pad4)") (class "Default")
      (node (ref "U21") (pin "4") (pinfunction "1C_4") (pintype "passive"))
    )
    (net (code "84") (name "unconnected-(U21-1D-Pad5)") (class "Default")
      (node (ref "U21") (pin "5") (pinfunction "1D_5") (pintype "passive"))
    )
    (net (code "85") (name "unconnected-(U21-2A-Pad9)") (class "Default")
      (node (ref "U21") (pin "9") (pinfunction "2A_9") (pintype "passive"))
    )
    (net (code "86") (name "unconnected-(U21-2B-Pad10)") (class "Default")
      (node (ref "U21") (pin "10") (pinfunction "2B_10") (pintype "passive"))
    )
    (net (code "87") (name "unconnected-(U21-2C-Pad12)") (class "Default")
      (node (ref "U21") (pin "12") (pinfunction "2C_12") (pintype "passive"))
    )
    (net (code "88") (name "unconnected-(U21-2D-Pad13)") (class "Default")
      (node (ref "U21") (pin "13") (pinfunction "2D_13") (pintype "passive"))
    )
    (net (code "89") (name "unconnected-(U21-2Y-Pad8)") (class "Default")
      (node (ref "U21") (pin "8") (pinfunction "2Y_8") (pintype "passive"))
    )
    (net (code "90") (name "unconnected-(U21-NC-Pad3)") (class "Default")
      (node (ref "U21") (pin "3") (pinfunction "NC_3") (pintype "passive"))
    )
    (net (code "91") (name "unconnected-(U21-NC-Pad11)") (class "Default")
      (node (ref "U21") (pin "11") (pinfunction "NC_11") (pintype "passive"))
    )
  )
)
